# CW308T_CEC1702_UFO.net
KiCad netlist of a schematic drawn in Altium Designer
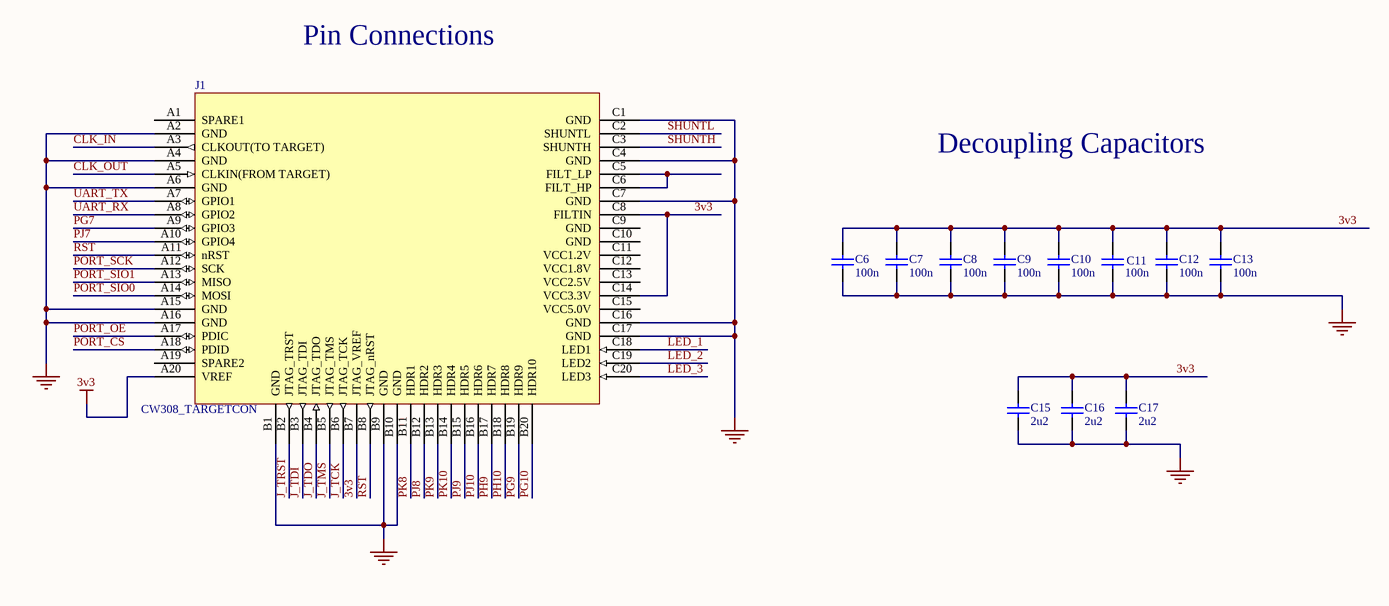
[diagram p0: CW308T_CEC1702_UFO.SchDoc]

(export (version "E")
  (design (tool "Eeschema 10.0.6"))
  (components
    (comp (ref "C6")
      (value "100n")
      (footprint "CAPC0603_M")
      (description "100n, 0603")
      (fields (field (name "PART NUMBER") "CCHIP-100n-0603"))
      (libsource (lib "NewAE_AltiumLib") (part "CAP"))
    )
    (comp (ref "C7")
      (value "100n")
      (footprint "CAPC0603_M")
      (description "100n, 0603")
      (fields (field (name "PART NUMBER") "CCHIP-100n-0603"))
      (libsource (lib "NewAE_AltiumLib") (part "CAP"))
    )
    (comp (ref "C8")
      (value "100n")
      (footprint "CAPC0603_M")
      (description "100n, 0603")
      (fields (field (name "PART NUMBER") "CCHIP-100n-0603"))
      (libsource (lib "NewAE_AltiumLib") (part "CAP"))
    )
    (comp (ref "C9")
      (value "100n")
      (footprint "CAPC0603_M")
      (description "100n, 0603")
      (fields (field (name "PART NUMBER") "CCHIP-100n-0603"))
      (libsource (lib "NewAE_AltiumLib") (part "CAP"))
    )
    (comp (ref "C10")
      (value "100n")
      (footprint "CAPC0603_M")
      (description "100n, 0603")
      (fields (field (name "PART NUMBER") "CCHIP-100n-0603"))
      (libsource (lib "NewAE_AltiumLib") (part "CAP"))
    )
    (comp (ref "C11")
      (value "100n")
      (footprint "CAPC0603_M")
      (description "100n, 0603")
      (fields (field (name "PART NUMBER") "CCHIP-100n-0603"))
      (libsource (lib "NewAE_AltiumLib") (part "CAP"))
    )
    (comp (ref "C12")
      (value "100n")
      (footprint "CAPC0603_M")
      (description "100n, 0603")
      (fields (field (name "PART NUMBER") "CCHIP-100n-0603"))
      (libsource (lib "NewAE_AltiumLib") (part "CAP"))
    )
    (comp (ref "C13")
      (value "100n")
      (footprint "CAPC0603_M")
      (description "100n, 0603")
      (fields (field (name "PART NUMBER") "CCHIP-100n-0603"))
      (libsource (lib "NewAE_AltiumLib") (part "CAP"))
    )
    (comp (ref "C15")
      (value "2u2")
      (footprint "CAPC0603_M")
      (description "2u2, 0603")
      (fields (field (name "PART NUMBER") "CCHIP-2u2-0603"))
      (libsource (lib "NewAE_AltiumLib") (part "CAP"))
    )
    (comp (ref "C16")
      (value "2u2")
      (footprint "CAPC0603_M")
      (description "2u2, 0603")
      (fields (field (name "PART NUMBER") "CCHIP-2u2-0603"))
      (libsource (lib "NewAE_AltiumLib") (part "CAP"))
    )
    (comp (ref "C17")
      (value "2u2")
      (footprint "CAPC0603_M")
      (description "2u2, 0603")
      (fields (field (name "PART NUMBER") "CCHIP-2u2-0603"))
      (libsource (lib "NewAE_AltiumLib") (part "CAP"))
    )
    (comp (ref "J1")
      (value "CW308_TARGETCON")
      (footprint "CW308_TBOARD_CONN")
      (description "CW308 \"Standard\" Target Board Connector")
      (fields (field (name "PART NUMBER") "CW308_TBOARD"))
      (libsource (lib "NewAE_AltiumLib") (part "CW308_TBOARD"))
    )
  )
  (nets
    (net (code "1") (name "/CLK_IN") (class "Default")
      (node (ref "J1") (pin "A3") (pinfunction "CLKOUT(TO_TARGET)_A3") (pintype "output"))
    )
    (net (code "2") (name "/CLK_OUT") (class "Default")
      (node (ref "J1") (pin "A5") (pinfunction "CLKIN(FROM_TARGET)_A5") (pintype "input"))
    )
    (net (code "3") (name "/J_TCK") (class "Default")
      (node (ref "J1") (pin "B6") (pinfunction "JTAG_TCK_B6") (pintype "output"))
    )
    (net (code "4") (name "/J_TDI") (class "Default")
      (node (ref "J1") (pin "B3") (pinfunction "JTAG_TDI_B3") (pintype "output"))
    )
    (net (code "5") (name "/J_TDO") (class "Default")
      (node (ref "J1") (pin "B4") (pinfunction "JTAG_TDO_B4") (pintype "input"))
    )
    (net (code "6") (name "/J_TMS") (class "Default")
      (node (ref "J1") (pin "B5") (pinfunction "JTAG_TMS_B5") (pintype "output"))
    )
    (net (code "7") (name "/J_TRST") (class "Default")
      (node (ref "J1") (pin "B2") (pinfunction "JTAG_TRST_B2") (pintype "output"))
    )
    (net (code "8") (name "/LED_1") (class "Default")
      (node (ref "J1") (pin "C18") (pinfunction "LED1_C18") (pintype "input"))
    )
    (net (code "9") (name "/LED_2") (class "Default")
      (node (ref "J1") (pin "C19") (pinfunction "LED2_C19") (pintype "input"))
    )
    (net (code "10") (name "/LED_3") (class "Default")
      (node (ref "J1") (pin "C20") (pinfunction "LED3_C20") (pintype "input"))
    )
    (net (code "11") (name "/PG7") (class "Default")
      (node (ref "J1") (pin "A9") (pinfunction "GPIO3_A9") (pintype "bidirectional"))
    )
    (net (code "12") (name "/PG9") (class "Default")
      (node (ref "J1") (pin "B19") (pinfunction "HDR9_B19") (pintype "passive"))
    )
    (net (code "13") (name "/PG10") (class "Default")
      (node (ref "J1") (pin "B20") (pinfunction "HDR10_B20") (pintype "passive"))
    )
    (net (code "14") (name "/PH9") (class "Default")
      (node (ref "J1") (pin "B17") (pinfunction "HDR7_B17") (pintype "passive"))
    )
    (net (code "15") (name "/PH10") (class "Default")
      (node (ref "J1") (pin "B18") (pinfunction "HDR8_B18") (pintype "passive"))
    )
    (net (code "16") (name "/PJ7") (class "Default")
      (node (ref "J1") (pin "A10") (pinfunction "GPIO4_A10") (pintype "bidirectional"))
    )
    (net (code "17") (name "/PJ8") (class "Default")
      (node (ref "J1") (pin "B12") (pinfunction "HDR2_B12") (pintype "passive"))
    )
    (net (code "18") (name "/PJ9") (class "Default")
      (node (ref "J1") (pin "B15") (pinfunction "HDR5_B15") (pintype "passive"))
    )
    (net (code "19") (name "/PJ10") (class "Default")
      (node (ref "J1") (pin "B16") (pinfunction "HDR6_B16") (pintype "passive"))
    )
    (net (code "20") (name "/PK8") (class "Default")
      (node (ref "J1") (pin "B11") (pinfunction "HDR1_B11") (pintype "passive"))
    )
    (net (code "21") (name "/PK9") (class "Default")
      (node (ref "J1") (pin "B13") (pinfunction "HDR3_B13") (pintype "passive"))
    )
    (net (code "22") (name "/PK10") (class "Default")
      (node (ref "J1") (pin "B14") (pinfunction "HDR4_B14") (pintype "passive"))
    )
    (net (code "23") (name "/PORT_CS") (class "Default")
      (node (ref "J1") (pin "A18") (pinfunction "PDID_A18") (pintype "bidirectional"))
    )
    (net (code "24") (name "/PORT_OE") (class "Default")
      (node (ref "J1") (pin "A17") (pinfunction "PDIC_A17") (pintype "bidirectional"))
    )
    (net (code "25") (name "/PORT_SCK") (class "Default")
      (node (ref "J1") (pin "A12") (pinfunction "SCK_A12") (pintype "bidirectional"))
    )
    (net (code "26") (name "/PORT_SIO0") (class "Default")
      (node (ref "J1") (pin "A14") (pinfunction "MOSI_A14") (pintype "bidirectional"))
    )
    (net (code "27") (name "/PORT_SIO1") (class "Default")
      (node (ref "J1") (pin "A13") (pinfunction "MISO_A13") (pintype "bidirectional"))
    )
    (net (code "28") (name "/RST") (class "Default")
      (node (ref "J1") (pin "A11") (pinfunction "nRST_A11") (pintype "bidirectional"))
      (node (ref "J1") (pin "B8") (pinfunction "JTAG_nRST_B8") (pintype "output"))
    )
    (net (code "29") (name "/SHUNTH") (class "Default")
      (node (ref "J1") (pin "C3") (pinfunction "SHUNTH_C3") (pintype "passive"))
    )
    (net (code "30") (name "/SHUNTL") (class "Default")
      (node (ref "J1") (pin "C2") (pinfunction "SHUNTL_C2") (pintype "passive"))
    )
    (net (code "31") (name "/UART_RX") (class "Default")
      (node (ref "J1") (pin "A8") (pinfunction "GPIO2_A8") (pintype "bidirectional"))
    )
    (net (code "32") (name "/UART_TX") (class "Default")
      (node (ref "J1") (pin "A7") (pinfunction "GPIO1_A7") (pintype "bidirectional"))
    )
    (net (code "33") (name "3v3") (class "Default")
      (node (ref "C10") (pin "1") (pinfunction "1_1") (pintype "passive"))
      (node (ref "C11") (pin "1") (pinfunction "1_1") (pintype "passive"))
      (node (ref "C12") (pin "1") (pinfunction "1_1") (pintype "passive"))
      (node (ref "C13") (pin "1") (pinfunction "1_1") (pintype "passive"))
      (node (ref "C15") (pin "1") (pinfunction "1_1") (pintype "passive"))
      (node (ref "C16") (pin "1") (pinfunction "1_1") (pintype "passive"))
      (node (ref "C17") (pin "1") (pinfunction "1_1") (pintype "passive"))
      (node (ref "C6") (pin "1") (pinfunction "1_1") (pintype "passive"))
      (node (ref "C7") (pin "1") (pinfunction "1_1") (pintype "passive"))
      (node (ref "C8") (pin "1") (pinfunction "1_1") (pintype "passive"))
      (node (ref "C9") (pin "1") (pinfunction "1_1") (pintype "passive"))
      (node (ref "J1") (pin "A20") (pinfunction "VREF_A20") (pintype "tri_state"))
      (node (ref "J1") (pin "B7") (pinfunction "JTAG_VREF_B7") (pintype "tri_state"))
      (node (ref "J1") (pin "C14") (pinfunction "VCC3.3V_C14") (pintype "power_in"))
      (node (ref "J1") (pin "C8") (pinfunction "FILTIN_C8") (pintype "passive"))
    )
    (net (code "34") (name "GND") (class "Default")
      (node (ref "C10") (pin "2") (pinfunction "2_2") (pintype "passive"))
      (node (ref "C11") (pin "2") (pinfunction "2_2") (pintype "passive"))
      (node (ref "C12") (pin "2") (pinfunction "2_2") (pintype "passive"))
      (node (ref "C13") (pin "2") (pinfunction "2_2") (pintype "passive"))
      (node (ref "C15") (pin "2") (pinfunction "2_2") (pintype "passive"))
      (node (ref "C16") (pin "2") (pinfunction "2_2") (pintype "passive"))
      (node (ref "C17") (pin "2") (pinfunction "2_2") (pintype "passive"))
      (node (ref "C6") (pin "2") (pinfunction "2_2") (pintype "passive"))
      (node (ref "C7") (pin "2") (pinfunction "2_2") (pintype "passive"))
      (node (ref "C8") (pin "2") (pinfunction "2_2") (pintype "passive"))
      (node (ref "C9") (pin "2") (pinfunction "2_2") (pintype "passive"))
      (node (ref "J1") (pin "A15") (pinfunction "GND_A15") (pintype "passive"))
      (node (ref "J1") (pin "A16") (pinfunction "GND_A16") (pintype "passive"))
      (node (ref "J1") (pin "A2") (pinfunction "GND_A2") (pintype "passive"))
      (node (ref "J1") (pin "A4") (pinfunction "GND_A4") (pintype "passive"))
      (node (ref "J1") (pin "A6") (pinfunction "GND_A6") (pintype "power_in"))
      (node (ref "J1") (pin "B1") (pinfunction "GND_B1") (pintype "passive"))
      (node (ref "J1") (pin "B10") (pinfunction "GND_B10") (pintype "passive"))
      (node (ref "J1") (pin "B9") (pinfunction "GND_B9") (pintype "passive"))
      (node (ref "J1") (pin "C1") (pinfunction "GND_C1") (pintype "power_in"))
      (node (ref "J1") (pin "C16") (pinfunction "GND_C16") (pintype "power_in"))
      (node (ref "J1") (pin "C17") (pinfunction "GND_C17") (pintype "power_in"))
      (node (ref "J1") (pin "C4") (pinfunction "GND_C4") (pintype "power_in"))
      (node (ref "J1") (pin "C7") (pinfunction "GND_C7") (pintype "power_in"))
    )
    (net (code "35") (name "Net-(J1-FILT_HP)") (class "Default")
      (node (ref "J1") (pin "C5") (pinfunction "FILT_LP_C5") (pintype "passive"))
      (node (ref "J1") (pin "C6") (pinfunction "FILT_HP_C6") (pintype "passive"))
    )
    (net (code "36") (name "unconnected-(J1-GND-PadC9)") (class "Default")
      (node (ref "J1") (pin "C9") (pinfunction "GND_C9") (pintype "power_in"))
    )
    (net (code "37") (name "unconnected-(J1-GND-PadC10)") (class "Default")
      (node (ref "J1") (pin "C10") (pinfunction "GND_C10") (pintype "power_in"))
    )
    (net (code "38") (name "unconnected-(J1-SPARE1-PadA1)") (class "Default")
      (node (ref "J1") (pin "A1") (pinfunction "SPARE1_A1") (pintype "passive"))
    )
    (net (code "39") (name "unconnected-(J1-SPARE2-PadA19)") (class "Default")
      (node (ref "J1") (pin "A19") (pinfunction "SPARE2_A19") (pintype "passive"))
    )
    (net (code "40") (name "unconnected-(J1-VCC1.2V-PadC11)") (class "Default")
      (node (ref "J1") (pin "C11") (pinfunction "VCC1.2V_C11") (pintype "power_in"))
    )
    (net (code "41") (name "unconnected-(J1-VCC1.8V-PadC12)") (class "Default")
      (node (ref "J1") (pin "C12") (pinfunction "VCC1.8V_C12") (pintype "power_in"))
    )
    (net (code "42") (name "unconnected-(J1-VCC2.5V-PadC13)") (class "Default")
      (node (ref "J1") (pin "C13") (pinfunction "VCC2.5V_C13") (pintype "power_in"))
    )
    (net (code "43") (name "unconnected-(J1-VCC5.0V-PadC15)") (class "Default")
      (node (ref "J1") (pin "C15") (pinfunction "VCC5.0V_C15") (pintype "power_in"))
    )
  )
)
